# 140508_AriloTX_REV2_0_0.net
KiCad netlist of a schematic drawn in EAGLE
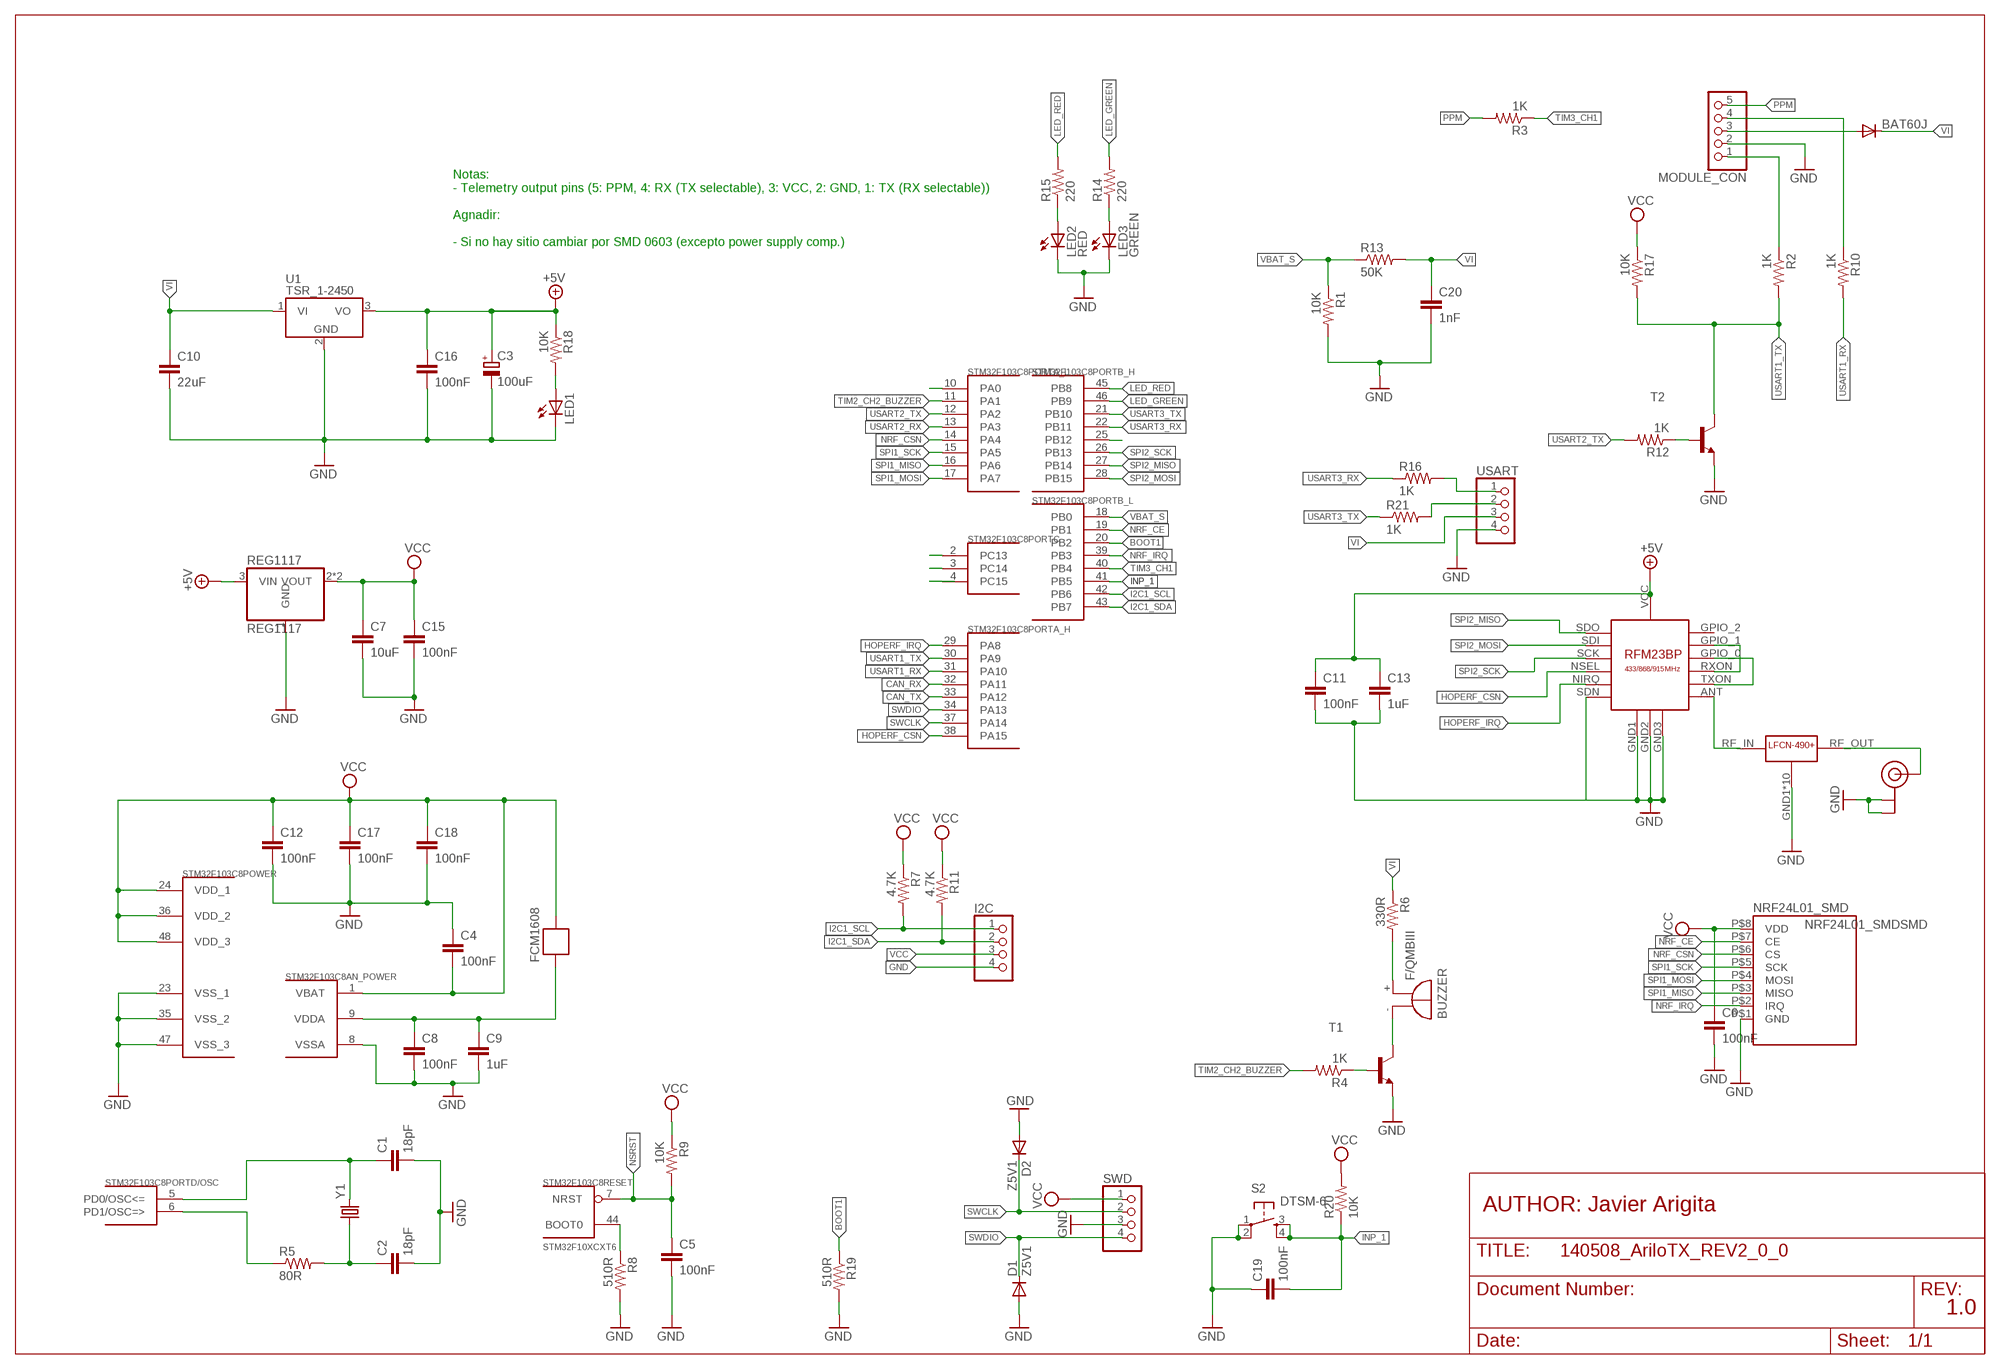
[diagram p0: schematic, sheet 1]

(export (version "E")
  (design (tool "Eeschema 10.0.6"))
  (components
    (comp (ref "BAT60J")
      (value "DIODE-SOD323-R")
      (footprint "eagle-import:SOD323-R")
      (libsource (lib "eagle-import") (part "DIODE-SOD323-R"))
    )
    (comp (ref "BUZZER")
      (value "F/QMBIII")
      (footprint "eagle-import:F_QMBIII")
      (libsource (lib "eagle-import") (part "F/QMBIII"))
    )
    (comp (ref "C1")
      (value "18pF")
      (footprint "eagle-import:C0805")
      (libsource (lib "eagle-import") (part "C-EUC0805"))
    )
    (comp (ref "C2")
      (value "18pF")
      (footprint "eagle-import:C0805")
      (libsource (lib "eagle-import") (part "C-EUC0805"))
    )
    (comp (ref "C3")
      (value "100uF")
      (footprint "eagle-import:SMC_B")
      (libsource (lib "eagle-import") (part "CPOL-EUSMCB"))
    )
    (comp (ref "C4")
      (value "100nF")
      (footprint "eagle-import:C0805")
      (libsource (lib "eagle-import") (part "C-EUC0805"))
    )
    (comp (ref "C5")
      (value "100nF")
      (footprint "eagle-import:C0805")
      (libsource (lib "eagle-import") (part "C-EUC0805"))
    )
    (comp (ref "C6")
      (value "100nF")
      (footprint "eagle-import:C0805")
      (libsource (lib "eagle-import") (part "C-EUC0805"))
    )
    (comp (ref "C7")
      (value "10uF")
      (footprint "eagle-import:C0805")
      (libsource (lib "eagle-import") (part "C-EUC0805"))
    )
    (comp (ref "C8")
      (value "100nF")
      (footprint "eagle-import:C0805")
      (libsource (lib "eagle-import") (part "C-EUC0805"))
    )
    (comp (ref "C9")
      (value "1uF")
      (footprint "eagle-import:C3216")
      (libsource (lib "eagle-import") (part "resistor_C-EUC3216"))
    )
    (comp (ref "C10")
      (value "22uF")
      (footprint "eagle-import:C3216")
      (libsource (lib "eagle-import") (part "resistor_C-EUC3216"))
    )
    (comp (ref "C11")
      (value "100nF")
      (footprint "eagle-import:C0805")
      (libsource (lib "eagle-import") (part "C-EUC0805"))
    )
    (comp (ref "C12")
      (value "100nF")
      (footprint "eagle-import:C0805")
      (libsource (lib "eagle-import") (part "C-EUC0805"))
    )
    (comp (ref "C13")
      (value "1uF")
      (footprint "eagle-import:C3216")
      (libsource (lib "eagle-import") (part "resistor_C-EUC3216"))
    )
    (comp (ref "C15")
      (value "100nF")
      (footprint "eagle-import:C0805")
      (libsource (lib "eagle-import") (part "C-EUC0805"))
    )
    (comp (ref "C16")
      (value "100nF")
      (footprint "eagle-import:C0805")
      (libsource (lib "eagle-import") (part "C-EUC0805"))
    )
    (comp (ref "C17")
      (value "100nF")
      (footprint "eagle-import:C0805")
      (libsource (lib "eagle-import") (part "C-EUC0805"))
    )
    (comp (ref "C18")
      (value "100nF")
      (footprint "eagle-import:C0805")
      (libsource (lib "eagle-import") (part "C-EUC0805"))
    )
    (comp (ref "C19")
      (value "100nF")
      (footprint "eagle-import:C0805")
      (libsource (lib "eagle-import") (part "C-EUC0805"))
    )
    (comp (ref "C20")
      (value "1nF")
      (footprint "eagle-import:C0805")
      (libsource (lib "eagle-import") (part "C-EUC0805"))
    )
    (comp (ref "D1")
      (value "Z5V1")
      (footprint "eagle-import:SOD323-R")
      (libsource (lib "eagle-import") (part "DIODE-SOD323-R"))
    )
    (comp (ref "D2")
      (value "Z5V1")
      (footprint "eagle-import:SOD323-R")
      (libsource (lib "eagle-import") (part "DIODE-SOD323-R"))
    )
    (comp (ref "FCM1608")
      (value "FERRITE-BEAD")
      (footprint "eagle-import:R0603")
      (libsource (lib "eagle-import") (part "FERRITE-BEAD"))
    )
    (comp (ref "I2C")
      (value "PINHD-1X4")
      (footprint "eagle-import:1X04")
      (libsource (lib "eagle-import") (part "PINHD-1X4"))
    )
    (comp (ref "LED1")
      (value "LED0805")
      (footprint "eagle-import:CHIPLED_0805")
      (libsource (lib "eagle-import") (part "LED0805"))
    )
    (comp (ref "LED2")
      (value "RED")
      (footprint "eagle-import:CHIP-LED0805")
      (libsource (lib "eagle-import") (part "LEDCHIP-LED0805"))
    )
    (comp (ref "LED3")
      (value "GREEN")
      (footprint "eagle-import:CHIP-LED0805")
      (libsource (lib "eagle-import") (part "LEDCHIP-LED0805"))
    )
    (comp (ref "MODULE_CON")
      (value "PINHD-1X5")
      (footprint "eagle-import:1X05")
      (libsource (lib "eagle-import") (part "PINHD-1X5"))
    )
    (comp (ref "NRF24L01_SMD")
      (value "NRF24L01_SMDSMD")
      (footprint "eagle-import:NRF24L01_SMD")
      (libsource (lib "eagle-import") (part "NRF24L01_SMDSMD"))
    )
    (comp (ref "R1")
      (value "10K")
      (footprint "eagle-import:R0805")
      (libsource (lib "eagle-import") (part "RESISTOR0805"))
    )
    (comp (ref "R2")
      (value "1K")
      (footprint "eagle-import:R0805")
      (libsource (lib "eagle-import") (part "RESISTOR0805"))
    )
    (comp (ref "R3")
      (value "1K")
      (footprint "eagle-import:R0805")
      (libsource (lib "eagle-import") (part "RESISTOR0805"))
    )
    (comp (ref "R4")
      (value "1K")
      (footprint "eagle-import:R0805")
      (libsource (lib "eagle-import") (part "RESISTOR0805"))
    )
    (comp (ref "R5")
      (value "80R")
      (footprint "eagle-import:R0805")
      (libsource (lib "eagle-import") (part "RESISTOR0805"))
    )
    (comp (ref "R6")
      (value "330R")
      (footprint "eagle-import:R0805")
      (libsource (lib "eagle-import") (part "RESISTOR0805"))
    )
    (comp (ref "R7")
      (value "4.7K")
      (footprint "eagle-import:R0805")
      (libsource (lib "eagle-import") (part "RESISTOR0805"))
    )
    (comp (ref "R8")
      (value "510R")
      (footprint "eagle-import:R0805")
      (libsource (lib "eagle-import") (part "RESISTOR0805"))
    )
    (comp (ref "R9")
      (value "10K")
      (footprint "eagle-import:R0805")
      (libsource (lib "eagle-import") (part "RESISTOR0805"))
    )
    (comp (ref "R10")
      (value "1K")
      (footprint "eagle-import:R0805")
      (libsource (lib "eagle-import") (part "RESISTOR0805"))
    )
    (comp (ref "R11")
      (value "4.7K")
      (footprint "eagle-import:R0805")
      (libsource (lib "eagle-import") (part "RESISTOR0805"))
    )
    (comp (ref "R12")
      (value "1K")
      (footprint "eagle-import:R0805")
      (libsource (lib "eagle-import") (part "RESISTOR0805"))
    )
    (comp (ref "R13")
      (value "50K")
      (footprint "eagle-import:R0805")
      (libsource (lib "eagle-import") (part "RESISTOR0805"))
    )
    (comp (ref "R14")
      (value "220")
      (footprint "eagle-import:R0805")
      (libsource (lib "eagle-import") (part "RESISTOR0805"))
    )
    (comp (ref "R15")
      (value "220")
      (footprint "eagle-import:R0805")
      (libsource (lib "eagle-import") (part "RESISTOR0805"))
    )
    (comp (ref "R16")
      (value "1K")
      (footprint "eagle-import:R0805")
      (libsource (lib "eagle-import") (part "RESISTOR0805"))
    )
    (comp (ref "R17")
      (value "10K")
      (footprint "eagle-import:R0805")
      (libsource (lib "eagle-import") (part "RESISTOR0805"))
    )
    (comp (ref "R18")
      (value "10K")
      (footprint "eagle-import:R0805")
      (libsource (lib "eagle-import") (part "RESISTOR0805"))
    )
    (comp (ref "R19")
      (value "510R")
      (footprint "eagle-import:R0805")
      (libsource (lib "eagle-import") (part "RESISTOR0805"))
    )
    (comp (ref "R20")
      (value "10K")
      (footprint "eagle-import:R0805")
      (libsource (lib "eagle-import") (part "RESISTOR0805"))
    )
    (comp (ref "R21")
      (value "1K")
      (footprint "eagle-import:R0805")
      (libsource (lib "eagle-import") (part "RESISTOR0805"))
    )
    (comp (ref "REG1117")
      (value "REG1117")
      (footprint "eagle-import:SOT223")
      (libsource (lib "eagle-import") (part "REG1117"))
    )
    (comp (ref "S2")
      (value "DTSM-6")
      (footprint "eagle-import:DTSM-6")
      (libsource (lib "eagle-import") (part "DTSM-6"))
    )
    (comp (ref "STM32F103C8")
      (value "STM32F10XCXT6")
      (footprint "eagle-import:TQFP48")
      (libsource (lib "eagle-import") (part "STM32F10XCXT6"))
    )
    (comp (ref "SWD")
      (value "PINHD-1X4")
      (footprint "eagle-import:1X04")
      (libsource (lib "eagle-import") (part "PINHD-1X4"))
    )
    (comp (ref "T1")
      (value "BC848-NPN-SOT23-BEC")
      (footprint "eagle-import:SOT23-BEC")
      (libsource (lib "eagle-import") (part "-NPN-SOT23-BECBC848"))
    )
    (comp (ref "T2")
      (value "BC848-NPN-SOT23-BEC")
      (footprint "eagle-import:SOT23-BEC")
      (libsource (lib "eagle-import") (part "-NPN-SOT23-BECBC848"))
    )
    (comp (ref "U$1")
      (value "RFM23BP")
      (footprint "eagle-import:RFM23BP")
      (libsource (lib "eagle-import") (part "RFM23BP"))
    )
    (comp (ref "U$2")
      (value "LFCN490+")
      (footprint "eagle-import:LFCN490+")
      (libsource (lib "eagle-import") (part "LFCN490+"))
    )
    (comp (ref "U$3")
      (value "U.FL")
      (footprint "eagle-import:U.FL")
      (libsource (lib "eagle-import") (part "U.FL"))
    )
    (comp (ref "U1")
      (value "TSR_1-2450")
      (footprint "eagle-import:TSR-1")
      (libsource (lib "eagle-import") (part "TSR_1-2450"))
    )
    (comp (ref "USART")
      (value "PINHD-1X4")
      (footprint "eagle-import:1X04")
      (libsource (lib "eagle-import") (part "PINHD-1X4"))
    )
    (comp (ref "Y1")
      (value "CRYSTAL5X3")
      (footprint "eagle-import:CRYSTAL-SMD-5X3")
      (libsource (lib "eagle-import") (part "CRYSTAL5X3"))
    )
  )
  (nets
    (net (code "1") (name "+5V") (class "Default")
      (node (ref "C11") (pin "1") (pinfunction "1_1") (pintype "passive"))
      (node (ref "C13") (pin "1") (pinfunction "1_1") (pintype "passive"))
      (node (ref "C16") (pin "1") (pinfunction "1_1") (pintype "passive"))
      (node (ref "C3") (pin "+") (pinfunction "+_+") (pintype "passive"))
      (node (ref "R18") (pin "1") (pinfunction "1_1") (pintype "passive"))
      (node (ref "REG1117") (pin "3") (pinfunction "VIN_3") (pintype "input"))
      (node (ref "U$1") (pin "VCC") (pinfunction "VCC_VCC") (pintype "power_in"))
      (node (ref "U1") (pin "3") (pinfunction "VO_3") (pintype "power_in"))
    )
    (net (code "2") (name "BOOT1") (class "Default")
      (node (ref "R19") (pin "1") (pinfunction "1_1") (pintype "passive"))
      (node (ref "STM32F103C8") (pin "20") (pinfunction "PB2_20") (pintype "bidirectional"))
    )
    (net (code "3") (name "CAN_RX") (class "Default")
      (node (ref "STM32F103C8") (pin "32") (pinfunction "PA11_32") (pintype "bidirectional"))
    )
    (net (code "4") (name "CAN_TX") (class "Default")
      (node (ref "STM32F103C8") (pin "33") (pinfunction "PA12_33") (pintype "bidirectional"))
    )
    (net (code "5") (name "GND") (class "Default")
      (node (ref "C1") (pin "2") (pinfunction "2_2") (pintype "passive"))
      (node (ref "C10") (pin "2") (pinfunction "2_2") (pintype "passive"))
      (node (ref "C11") (pin "2") (pinfunction "2_2") (pintype "passive"))
      (node (ref "C12") (pin "2") (pinfunction "2_2") (pintype "passive"))
      (node (ref "C13") (pin "2") (pinfunction "2_2") (pintype "passive"))
      (node (ref "C15") (pin "2") (pinfunction "2_2") (pintype "passive"))
      (node (ref "C16") (pin "2") (pinfunction "2_2") (pintype "passive"))
      (node (ref "C17") (pin "2") (pinfunction "2_2") (pintype "passive"))
      (node (ref "C18") (pin "2") (pinfunction "2_2") (pintype "passive"))
      (node (ref "C19") (pin "1") (pinfunction "1_1") (pintype "passive"))
      (node (ref "C2") (pin "2") (pinfunction "2_2") (pintype "passive"))
      (node (ref "C20") (pin "2") (pinfunction "2_2") (pintype "passive"))
      (node (ref "C3") (pin "-") (pinfunction "-_-") (pintype "passive"))
      (node (ref "C4") (pin "1") (pinfunction "1_1") (pintype "passive"))
      (node (ref "C5") (pin "2") (pinfunction "2_2") (pintype "passive"))
      (node (ref "C6") (pin "2") (pinfunction "2_2") (pintype "passive"))
      (node (ref "C7") (pin "2") (pinfunction "2_2") (pintype "passive"))
      (node (ref "C8") (pin "2") (pinfunction "2_2") (pintype "passive"))
      (node (ref "C9") (pin "2") (pinfunction "2_2") (pintype "passive"))
      (node (ref "D1") (pin "A") (pinfunction "A_A") (pintype "passive"))
      (node (ref "D2") (pin "A") (pinfunction "A_A") (pintype "passive"))
      (node (ref "I2C") (pin "4") (pinfunction "4_4") (pintype "passive"))
      (node (ref "LED1") (pin "C") (pinfunction "C_C") (pintype "passive"))
      (node (ref "LED2") (pin "C") (pinfunction "C_C") (pintype "passive"))
      (node (ref "LED3") (pin "C") (pinfunction "C_C") (pintype "passive"))
      (node (ref "MODULE_CON") (pin "2") (pinfunction "2_2") (pintype "passive"))
      (node (ref "NRF24L01_SMD") (pin "P$1") (pinfunction "GND_P$1") (pintype "power_in"))
      (node (ref "R1") (pin "2") (pinfunction "2_2") (pintype "passive"))
      (node (ref "R19") (pin "2") (pinfunction "2_2") (pintype "passive"))
      (node (ref "R8") (pin "2") (pinfunction "2_2") (pintype "passive"))
      (node (ref "REG1117") (pin "1") (pinfunction "GND_1") (pintype "power_in"))
      (node (ref "S2") (pin "1") (pinfunction "1_1") (pintype "passive"))
      (node (ref "S2") (pin "2") (pinfunction "2_2") (pintype "passive"))
      (node (ref "STM32F103C8") (pin "23") (pinfunction "VSS_1_23") (pintype "power_in"))
      (node (ref "STM32F103C8") (pin "35") (pinfunction "VSS_2_35") (pintype "power_in"))
      (node (ref "STM32F103C8") (pin "47") (pinfunction "VSS_3_47") (pintype "power_in"))
      (node (ref "STM32F103C8") (pin "8") (pinfunction "VSSA_8") (pintype "power_in"))
      (node (ref "SWD") (pin "3") (pinfunction "3_3") (pintype "passive"))
      (node (ref "T1") (pin "E") (pinfunction "E_E") (pintype "passive"))
      (node (ref "T2") (pin "E") (pinfunction "E_E") (pintype "passive"))
      (node (ref "U$1") (pin "GND1") (pinfunction "GND1_GND1") (pintype "power_in"))
      (node (ref "U$1") (pin "GND2") (pinfunction "GND2_GND2") (pintype "power_in"))
      (node (ref "U$1") (pin "GND3") (pinfunction "GND3_GND3") (pintype "power_in"))
      (node (ref "U$1") (pin "SDN") (pinfunction "SDN_SDN") (pintype "bidirectional"))
      (node (ref "U$2") (pin "GND1") (pinfunction "GND_GND1") (pintype "bidirectional"))
      (node (ref "U$2") (pin "GND10") (pinfunction "GND_GND10") (pintype "bidirectional"))
      (node (ref "U$2") (pin "GND2") (pinfunction "GND_GND2") (pintype "bidirectional"))
      (node (ref "U$2") (pin "GND3") (pinfunction "GND_GND3") (pintype "bidirectional"))
      (node (ref "U$2") (pin "GND4") (pinfunction "GND_GND4") (pintype "bidirectional"))
      (node (ref "U$2") (pin "GND5") (pinfunction "GND_GND5") (pintype "bidirectional"))
      (node (ref "U$2") (pin "GND6") (pinfunction "GND_GND6") (pintype "bidirectional"))
      (node (ref "U$2") (pin "GND7") (pinfunction "GND_GND7") (pintype "bidirectional"))
      (node (ref "U$2") (pin "GND8") (pinfunction "GND_GND8") (pintype "bidirectional"))
      (node (ref "U$2") (pin "GND9") (pinfunction "GND_GND9") (pintype "bidirectional"))
      (node (ref "U$3") (pin "P$1") (pinfunction "GND_P$1") (pintype "bidirectional"))
      (node (ref "U$3") (pin "P$2") (pinfunction "GND_P$2") (pintype "bidirectional"))
      (node (ref "U1") (pin "2") (pinfunction "GND_2") (pintype "power_in"))
      (node (ref "USART") (pin "4") (pinfunction "4_4") (pintype "passive"))
    )
    (net (code "6") (name "HOPERF_CSN") (class "Default")
      (node (ref "STM32F103C8") (pin "38") (pinfunction "PA15_38") (pintype "bidirectional"))
      (node (ref "U$1") (pin "NSEL") (pinfunction "NSEL_NSEL") (pintype "bidirectional"))
    )
    (net (code "7") (name "HOPERF_IRQ") (class "Default")
      (node (ref "STM32F103C8") (pin "29") (pinfunction "PA8_29") (pintype "bidirectional"))
      (node (ref "U$1") (pin "NIRQ") (pinfunction "NIRQ_NIRQ") (pintype "bidirectional"))
    )
    (net (code "8") (name "I2C1_SCL") (class "Default")
      (node (ref "I2C") (pin "1") (pinfunction "1_1") (pintype "passive"))
      (node (ref "R7") (pin "2") (pinfunction "2_2") (pintype "passive"))
      (node (ref "STM32F103C8") (pin "42") (pinfunction "PB6_42") (pintype "bidirectional"))
    )
    (net (code "9") (name "I2C1_SDA") (class "Default")
      (node (ref "I2C") (pin "2") (pinfunction "2_2") (pintype "passive"))
      (node (ref "R11") (pin "2") (pinfunction "2_2") (pintype "passive"))
      (node (ref "STM32F103C8") (pin "43") (pinfunction "PB7_43") (pintype "bidirectional"))
    )
    (net (code "10") (name "INP_1") (class "Default")
      (node (ref "C19") (pin "2") (pinfunction "2_2") (pintype "passive"))
      (node (ref "R20") (pin "1") (pinfunction "1_1") (pintype "passive"))
      (node (ref "S2") (pin "3") (pinfunction "3_3") (pintype "passive"))
      (node (ref "S2") (pin "4") (pinfunction "4_4") (pintype "passive"))
      (node (ref "STM32F103C8") (pin "41") (pinfunction "PB5_41") (pintype "bidirectional"))
    )
    (net (code "11") (name "LED_GREEN") (class "Default")
      (node (ref "R14") (pin "2") (pinfunction "2_2") (pintype "passive"))
      (node (ref "STM32F103C8") (pin "46") (pinfunction "PB9_46") (pintype "bidirectional"))
    )
    (net (code "12") (name "LED_RED") (class "Default")
      (node (ref "R15") (pin "2") (pinfunction "2_2") (pintype "passive"))
      (node (ref "STM32F103C8") (pin "45") (pinfunction "PB8_45") (pintype "bidirectional"))
    )
    (net (code "13") (name "NRF_CE") (class "Default")
      (node (ref "NRF24L01_SMD") (pin "P$7") (pinfunction "CE_P$7") (pintype "input"))
      (node (ref "STM32F103C8") (pin "19") (pinfunction "PB1_19") (pintype "bidirectional"))
    )
    (net (code "14") (name "NRF_CSN") (class "Default")
      (node (ref "NRF24L01_SMD") (pin "P$6") (pinfunction "CS_P$6") (pintype "input"))
      (node (ref "STM32F103C8") (pin "14") (pinfunction "PA4_14") (pintype "bidirectional"))
    )
    (net (code "15") (name "NRF_IRQ") (class "Default")
      (node (ref "NRF24L01_SMD") (pin "P$2") (pinfunction "IRQ_P$2") (pintype "output"))
      (node (ref "STM32F103C8") (pin "39") (pinfunction "PB3_39") (pintype "bidirectional"))
    )
    (net (code "16") (name "NSRST") (class "Default")
      (node (ref "C5") (pin "1") (pinfunction "1_1") (pintype "passive"))
      (node (ref "R9") (pin "2") (pinfunction "2_2") (pintype "passive"))
      (node (ref "STM32F103C8") (pin "7") (pinfunction "NRST_7") (pintype "input"))
    )
    (net (code "17") (name "Net-(BAT60J-PadA)") (class "Default")
      (node (ref "BAT60J") (pin "A") (pinfunction "A_A") (pintype "passive"))
      (node (ref "MODULE_CON") (pin "3") (pinfunction "3_3") (pintype "passive"))
    )
    (net (code "18") (name "Net-(BUZZER-+)") (class "Default")
      (node (ref "BUZZER") (pin "-") (pinfunction "+_-") (pintype "passive"))
      (node (ref "T1") (pin "C") (pinfunction "C_C") (pintype "passive"))
    )
    (net (code "19") (name "Net-(BUZZER--)") (class "Default")
      (node (ref "BUZZER") (pin "+") (pinfunction "-_+") (pintype "passive"))
      (node (ref "R6") (pin "2") (pinfunction "2_2") (pintype "passive"))
    )
    (net (code "20") (name "Net-(C2-Pad1)") (class "Default")
      (node (ref "C2") (pin "1") (pinfunction "1_1") (pintype "passive"))
      (node (ref "R5") (pin "2") (pinfunction "2_2") (pintype "passive"))
      (node (ref "Y1") (pin "1") (pinfunction "1_1") (pintype "passive"))
    )
    (net (code "21") (name "Net-(FCM1608-P$2)") (class "Default")
      (node (ref "C8") (pin "1") (pinfunction "1_1") (pintype "passive"))
      (node (ref "C9") (pin "1") (pinfunction "1_1") (pintype "passive"))
      (node (ref "FCM1608") (pin "2") (pinfunction "P$2_2") (pintype "bidirectional"))
      (node (ref "STM32F103C8") (pin "9") (pinfunction "VDDA_9") (pintype "power_in"))
    )
    (net (code "22") (name "Net-(LED1-PadA)") (class "Default")
      (node (ref "LED1") (pin "A") (pinfunction "A_A") (pintype "passive"))
      (node (ref "R18") (pin "2") (pinfunction "2_2") (pintype "passive"))
    )
    (net (code "23") (name "Net-(LED2-PadA)") (class "Default")
      (node (ref "LED2") (pin "A") (pinfunction "A_A") (pintype "passive"))
      (node (ref "R15") (pin "1") (pinfunction "1_1") (pintype "passive"))
    )
    (net (code "24") (name "Net-(LED3-PadA)") (class "Default")
      (node (ref "LED3") (pin "A") (pinfunction "A_A") (pintype "passive"))
      (node (ref "R14") (pin "1") (pinfunction "1_1") (pintype "passive"))
    )
    (net (code "25") (name "Net-(MODULE_CON-Pad1)") (class "Default")
      (node (ref "MODULE_CON") (pin "1") (pinfunction "1_1") (pintype "passive"))
      (node (ref "R2") (pin "1") (pinfunction "1_1") (pintype "passive"))
    )
    (net (code "26") (name "Net-(MODULE_CON-Pad4)") (class "Default")
      (node (ref "MODULE_CON") (pin "4") (pinfunction "4_4") (pintype "passive"))
      (node (ref "R10") (pin "1") (pinfunction "1_1") (pintype "passive"))
    )
    (net (code "27") (name "Net-(R4-Pad1)") (class "Default")
      (node (ref "R4") (pin "1") (pinfunction "1_1") (pintype "passive"))
      (node (ref "T1") (pin "B") (pinfunction "B_B") (pintype "passive"))
    )
    (net (code "28") (name "Net-(R12-Pad1)") (class "Default")
      (node (ref "R12") (pin "1") (pinfunction "1_1") (pintype "passive"))
      (node (ref "T2") (pin "B") (pinfunction "B_B") (pintype "passive"))
    )
    (net (code "29") (name "Net-(R16-Pad2)") (class "Default")
      (node (ref "R16") (pin "2") (pinfunction "2_2") (pintype "passive"))
      (node (ref "USART") (pin "1") (pinfunction "1_1") (pintype "passive"))
    )
    (net (code "30") (name "Net-(R21-Pad2)") (class "Default")
      (node (ref "R21") (pin "2") (pinfunction "2_2") (pintype "passive"))
      (node (ref "USART") (pin "2") (pinfunction "2_2") (pintype "passive"))
    )
    (net (code "31") (name "Net-(STM32F103C8G-PD0{slash}OSC<=)") (class "Default")
      (node (ref "C1") (pin "1") (pinfunction "1_1") (pintype "passive"))
      (node (ref "STM32F103C8") (pin "5") (pinfunction "PD0/OSC<=_5") (pintype "bidirectional"))
      (node (ref "Y1") (pin "3") (pinfunction "2_3") (pintype "passive"))
    )
    (net (code "32") (name "Net-(STM32F103C8G-PD1{slash}OSC=>)") (class "Default")
      (node (ref "R5") (pin "1") (pinfunction "1_1") (pintype "passive"))
      (node (ref "STM32F103C8") (pin "6") (pinfunction "PD1/OSC=>_6") (pintype "bidirectional"))
    )
    (net (code "33") (name "Net-(STM32F103C8I-BOOT0)") (class "Default")
      (node (ref "R8") (pin "1") (pinfunction "1_1") (pintype "passive"))
      (node (ref "STM32F103C8") (pin "44") (pinfunction "BOOT0_44") (pintype "input"))
    )
    (net (code "34") (name "Net-(U$1-PadGPIO_0)") (class "Default")
      (node (ref "U$1") (pin "GPIO_0") (pinfunction "GPIO_0_GPIO_0") (pintype "bidirectional"))
      (node (ref "U$1") (pin "TXON") (pinfunction "TXON_TXON") (pintype "bidirectional"))
    )
    (net (code "35") (name "Net-(U$1-PadGPIO_1)") (class "Default")
      (node (ref "U$1") (pin "GPIO_1") (pinfunction "GPIO_1_GPIO_1") (pintype "bidirectional"))
      (node (ref "U$1") (pin "RXON") (pinfunction "RXON_RXON") (pintype "bidirectional"))
    )
    (net (code "36") (name "Net-(U$2-RF_INP)") (class "Default")
      (node (ref "U$1") (pin "ANT") (pinfunction "ANT_ANT") (pintype "bidirectional"))
      (node (ref "U$2") (pin "RF_IN") (pinfunction "RF_INP_RF_IN") (pintype "bidirectional"))
    )
    (net (code "37") (name "Net-(U$2-RF_OUTP)") (class "Default")
      (node (ref "U$2") (pin "RF_OUT") (pinfunction "RF_OUTP_RF_OUT") (pintype "bidirectional"))
      (node (ref "U$3") (pin "P$3") (pinfunction "SIGNAL_P$3") (pintype "bidirectional"))
    )
    (net (code "38") (name "PPM") (class "Default")
      (node (ref "MODULE_CON") (pin "5") (pinfunction "5_5") (pintype "passive"))
      (node (ref "R3") (pin "2") (pinfunction "2_2") (pintype "passive"))
    )
    (net (code "39") (name "SPI1_MISO") (class "Default")
      (node (ref "NRF24L01_SMD") (pin "P$3") (pinfunction "MISO_P$3") (pintype "output"))
      (node (ref "STM32F103C8") (pin "16") (pinfunction "PA6_16") (pintype "bidirectional"))
    )
    (net (code "40") (name "SPI1_MOSI") (class "Default")
      (node (ref "NRF24L01_SMD") (pin "P$4") (pinfunction "MOSI_P$4") (pintype "input"))
      (node (ref "STM32F103C8") (pin "17") (pinfunction "PA7_17") (pintype "bidirectional"))
    )
    (net (code "41") (name "SPI1_SCK") (class "Default")
      (node (ref "NRF24L01_SMD") (pin "P$5") (pinfunction "SCK_P$5") (pintype "input"))
      (node (ref "STM32F103C8") (pin "15") (pinfunction "PA5_15") (pintype "bidirectional"))
    )
    (net (code "42") (name "SPI2_MISO") (class "Default")
      (node (ref "STM32F103C8") (pin "27") (pinfunction "PB14_27") (pintype "bidirectional"))
      (node (ref "U$1") (pin "SDO") (pinfunction "SDO_SDO") (pintype "bidirectional"))
    )
    (net (code "43") (name "SPI2_MOSI") (class "Default")
      (node (ref "STM32F103C8") (pin "28") (pinfunction "PB15_28") (pintype "bidirectional"))
      (node (ref "U$1") (pin "SDI") (pinfunction "SDI_SDI") (pintype "bidirectional"))
    )
    (net (code "44") (name "SPI2_SCK") (class "Default")
      (node (ref "STM32F103C8") (pin "26") (pinfunction "PB13_26") (pintype "bidirectional"))
      (node (ref "U$1") (pin "SCK") (pinfunction "SCK_SCK") (pintype "bidirectional"))
    )
    (net (code "45") (name "SWCLK") (class "Default")
      (node (ref "D2") (pin "C") (pinfunction "C_C") (pintype "passive"))
      (node (ref "STM32F103C8") (pin "37") (pinfunction "PA14_37") (pintype "bidirectional"))
      (node (ref "SWD") (pin "2") (pinfunction "2_2") (pintype "passive"))
    )
    (net (code "46") (name "SWDIO") (class "Default")
      (node (ref "D1") (pin "C") (pinfunction "C_C") (pintype "passive"))
      (node (ref "STM32F103C8") (pin "34") (pinfunction "PA13_34") (pintype "bidirectional"))
      (node (ref "SWD") (pin "4") (pinfunction "4_4") (pintype "passive"))
    )
    (net (code "47") (name "TIM2_CH2_BUZZER") (class "Default")
      (node (ref "R4") (pin "2") (pinfunction "2_2") (pintype "passive"))
      (node (ref "STM32F103C8") (pin "11") (pinfunction "PA1_11") (pintype "bidirectional"))
    )
    (net (code "48") (name "TIM3_CH1") (class "Default")
      (node (ref "R3") (pin "1") (pinfunction "1_1") (pintype "passive"))
      (node (ref "STM32F103C8") (pin "40") (pinfunction "PB4_40") (pintype "bidirectional"))
    )
    (net (code "49") (name "USART1_RX") (class "Default")
      (node (ref "R10") (pin "2") (pinfunction "2_2") (pintype "passive"))
      (node (ref "STM32F103C8") (pin "31") (pinfunction "PA10_31") (pintype "bidirectional"))
    )
    (net (code "50") (name "USART1_TX") (class "Default")
      (node (ref "R17") (pin "2") (pinfunction "2_2") (pintype "passive"))
      (node (ref "R2") (pin "2") (pinfunction "2_2") (pintype "passive"))
      (node (ref "STM32F103C8") (pin "30") (pinfunction "PA9_30") (pintype "bidirectional"))
      (node (ref "T2") (pin "C") (pinfunction "C_C") (pintype "passive"))
    )
    (net (code "51") (name "USART2_RX") (class "Default")
      (node (ref "STM32F103C8") (pin "13") (pinfunction "PA3_13") (pintype "bidirectional"))
    )
    (net (code "52") (name "USART2_TX") (class "Default")
      (node (ref "R12") (pin "2") (pinfunction "2_2") (pintype "passive"))
      (node (ref "STM32F103C8") (pin "12") (pinfunction "PA2_12") (pintype "bidirectional"))
    )
    (net (code "53") (name "USART3_RX") (class "Default")
      (node (ref "R16") (pin "1") (pinfunction "1_1") (pintype "passive"))
      (node (ref "STM32F103C8") (pin "22") (pinfunction "PB11_22") (pintype "bidirectional"))
    )
    (net (code "54") (name "USART3_TX") (class "Default")
      (node (ref "R21") (pin "1") (pinfunction "1_1") (pintype "passive"))
      (node (ref "STM32F103C8") (pin "21") (pinfunction "PB10_21") (pintype "bidirectional"))
    )
    (net (code "55") (name "VBAT_S") (class "Default")
      (node (ref "R1") (pin "1") (pinfunction "1_1") (pintype "passive"))
      (node (ref "R13") (pin "1") (pinfunction "1_1") (pintype "passive"))
      (node (ref "STM32F103C8") (pin "18") (pinfunction "PB0_18") (pintype "bidirectional"))
    )
    (net (code "56") (name "VCC") (class "Default")
      (node (ref "C12") (pin "1") (pinfunction "1_1") (pintype "passive"))
      (node (ref "C15") (pin "1") (pinfunction "1_1") (pintype "passive"))
      (node (ref "C17") (pin "1") (pinfunction "1_1") (pintype "passive"))
      (node (ref "C18") (pin "1") (pinfunction "1_1") (pintype "passive"))
      (node (ref "C4") (pin "2") (pinfunction "2_2") (pintype "passive"))
      (node (ref "C6") (pin "1") (pinfunction "1_1") (pintype "passive"))
      (node (ref "C7") (pin "1") (pinfunction "1_1") (pintype "passive"))
      (node (ref "FCM1608") (pin "1") (pinfunction "P$1_1") (pintype "bidirectional"))
      (node (ref "I2C") (pin "3") (pinfunction "3_3") (pintype "passive"))
      (node (ref "NRF24L01_SMD") (pin "P$8") (pinfunction "VDD_P$8") (pintype "bidirectional"))
      (node (ref "R11") (pin "1") (pinfunction "1_1") (pintype "passive"))
      (node (ref "R17") (pin "1") (pinfunction "1_1") (pintype "passive"))
      (node (ref "R20") (pin "2") (pinfunction "2_2") (pintype "passive"))
      (node (ref "R7") (pin "1") (pinfunction "1_1") (pintype "passive"))
      (node (ref "R9") (pin "1") (pinfunction "1_1") (pintype "passive"))
      (node (ref "REG1117") (pin "2") (pinfunction "VOUT_2") (pintype "power_in"))
      (node (ref "REG1117") (pin "4") (pinfunction "VOUT_4") (pintype "power_in"))
      (node (ref "STM32F103C8") (pin "1") (pinfunction "VBAT_1") (pintype "power_in"))
      (node (ref "STM32F103C8") (pin "24") (pinfunction "VDD_1_24") (pintype "power_in"))
      (node (ref "STM32F103C8") (pin "36") (pinfunction "VDD_2_36") (pintype "power_in"))
      (node (ref "STM32F103C8") (pin "48") (pinfunction "VDD_3_48") (pintype "power_in"))
      (node (ref "SWD") (pin "1") (pinfunction "1_1") (pintype "passive"))
    )
    (net (code "57") (name "VI") (class "Default")
      (node (ref "BAT60J") (pin "C") (pinfunction "C_C") (pintype "passive"))
      (node (ref "C10") (pin "1") (pinfunction "1_1") (pintype "passive"))
      (node (ref "C20") (pin "1") (pinfunction "1_1") (pintype "passive"))
      (node (ref "R13") (pin "2") (pinfunction "2_2") (pintype "passive"))
      (node (ref "R6") (pin "1") (pinfunction "1_1") (pintype "passive"))
      (node (ref "U1") (pin "1") (pinfunction "VI_1") (pintype "power_in"))
      (node (ref "USART") (pin "3") (pinfunction "3_3") (pintype "passive"))
    )
    (net (code "58") (name "unconnected-(STM32F103C8C-PA0-Pad10)") (class "Default")
      (node (ref "STM32F103C8") (pin "10") (pinfunction "PA0_10") (pintype "bidirectional"))
    )
    (net (code "59") (name "unconnected-(STM32F103C8D-PB12-Pad25)") (class "Default")
      (node (ref "STM32F103C8") (pin "25") (pinfunction "PB12_25") (pintype "bidirectional"))
    )
    (net (code "60") (name "unconnected-(STM32F103C8F-PC13-Pad2)") (class "Default")
      (node (ref "STM32F103C8") (pin "2") (pinfunction "PC13_2") (pintype "bidirectional"))
    )
    (net (code "61") (name "unconnected-(STM32F103C8F-PC14-Pad3)") (class "Default")
      (node (ref "STM32F103C8") (pin "3") (pinfunction "PC14_3") (pintype "bidirectional"))
    )
    (net (code "62") (name "unconnected-(STM32F103C8F-PC15-Pad4)") (class "Default")
      (node (ref "STM32F103C8") (pin "4") (pinfunction "PC15_4") (pintype "bidirectional"))
    )
    (net (code "63") (name "unconnected-(U$1-PadGPIO_2)") (class "Default")
      (node (ref "U$1") (pin "GPIO_2") (pinfunction "GPIO_2_GPIO_2") (pintype "bidirectional"))
    )
  )
)
